# suliss-sensor-board.net
KiCad netlist of a schematic drawn in EAGLE
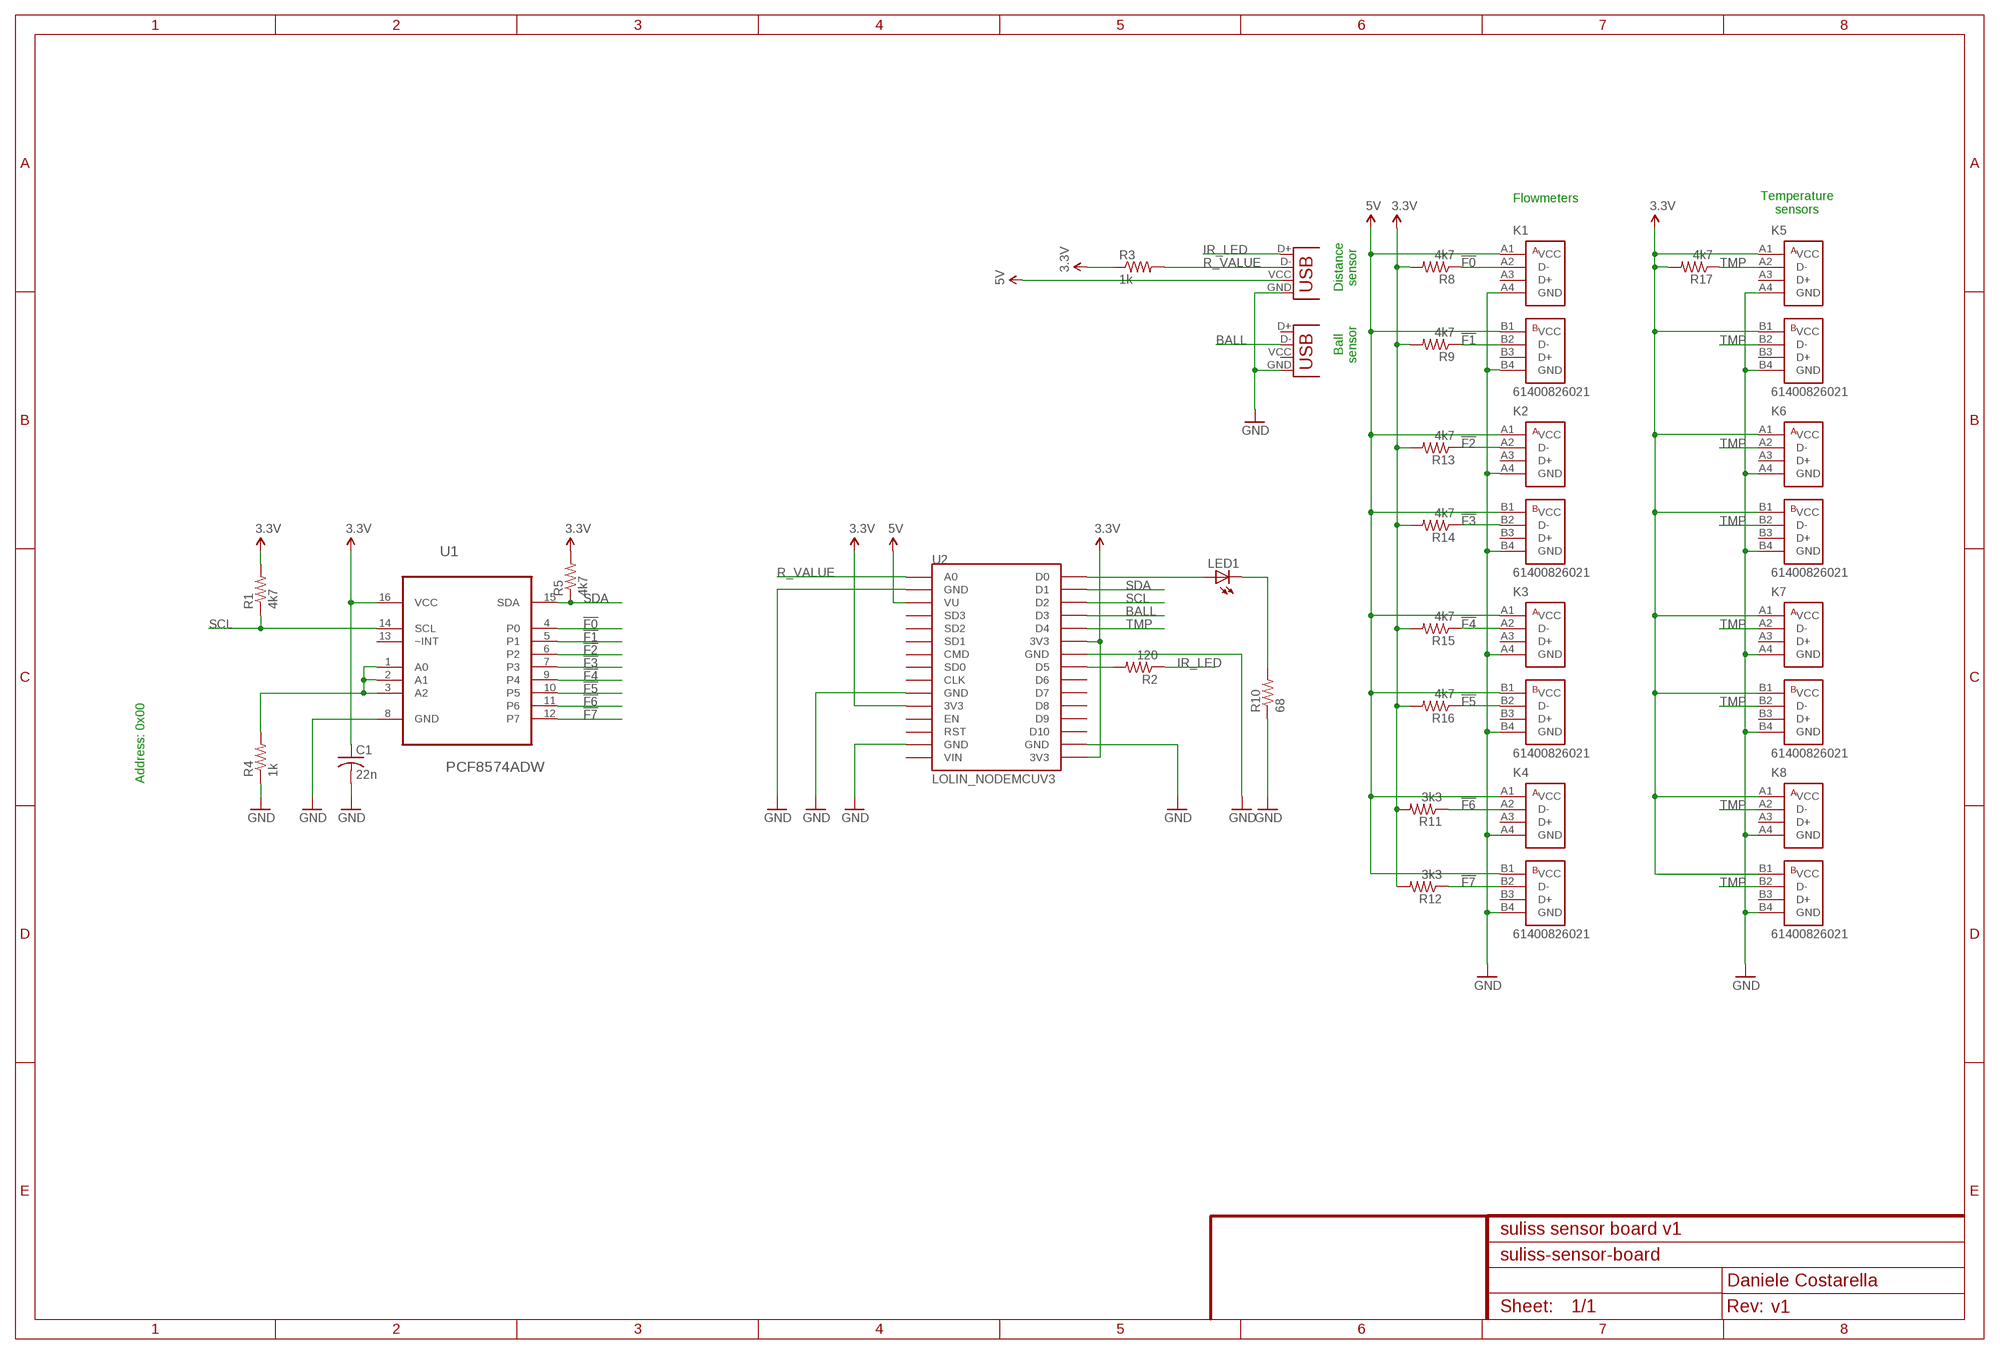
[diagram p0: schematic, sheet 1]

(export (version "E")
  (design (tool "Eeschema 10.0.6"))
  (components
    (comp (ref "C1")
      (value "22n")
      (footprint "eagle-import:C1206")
      (libsource (lib "eagle-import") (part "C-USC1206"))
    )
    (comp (ref "JP1")
      (value "USB-A-H")
      (footprint "eagle-import:USB-A-VERT")
      (libsource (lib "eagle-import") (part "USB-A-H"))
    )
    (comp (ref "JP2")
      (value "USB-A-H")
      (footprint "eagle-import:USB-A-VERT")
      (libsource (lib "eagle-import") (part "USB-A-H"))
    )
    (comp (ref "K1")
      (value "61400826021")
      (footprint "eagle-import:61400826021")
      (libsource (lib "eagle-import") (part "61400826021"))
    )
    (comp (ref "K2")
      (value "61400826021")
      (footprint "eagle-import:61400826021")
      (libsource (lib "eagle-import") (part "61400826021"))
    )
    (comp (ref "K3")
      (value "61400826021")
      (footprint "eagle-import:61400826021")
      (libsource (lib "eagle-import") (part "61400826021"))
    )
    (comp (ref "K4")
      (value "61400826021")
      (footprint "eagle-import:61400826021")
      (libsource (lib "eagle-import") (part "61400826021"))
    )
    (comp (ref "K5")
      (value "61400826021")
      (footprint "eagle-import:61400826021")
      (libsource (lib "eagle-import") (part "61400826021"))
    )
    (comp (ref "K6")
      (value "61400826021")
      (footprint "eagle-import:61400826021")
      (libsource (lib "eagle-import") (part "61400826021"))
    )
    (comp (ref "K7")
      (value "61400826021")
      (footprint "eagle-import:61400826021")
      (libsource (lib "eagle-import") (part "61400826021"))
    )
    (comp (ref "K8")
      (value "61400826021")
      (footprint "eagle-import:61400826021")
      (libsource (lib "eagle-import") (part "61400826021"))
    )
    (comp (ref "LED1")
      (value "LEDCHIP-LED0603")
      (footprint "eagle-import:CHIP-LED0603")
      (libsource (lib "eagle-import") (part "LEDCHIP-LED0603"))
    )
    (comp (ref "R1")
      (value "4k7")
      (footprint "eagle-import:R0603")
      (libsource (lib "eagle-import") (part "R-US_R0603"))
    )
    (comp (ref "R2")
      (value "120")
      (footprint "eagle-import:R0603")
      (libsource (lib "eagle-import") (part "R-US_R0603"))
    )
    (comp (ref "R3")
      (value "1k")
      (footprint "eagle-import:R0603")
      (libsource (lib "eagle-import") (part "R-US_R0603"))
    )
    (comp (ref "R4")
      (value "1k")
      (footprint "eagle-import:R0603")
      (libsource (lib "eagle-import") (part "R-US_R0603"))
    )
    (comp (ref "R5")
      (value "4k7")
      (footprint "eagle-import:R0603")
      (libsource (lib "eagle-import") (part "R-US_R0603"))
    )
    (comp (ref "R8")
      (value "4k7")
      (footprint "eagle-import:R0603")
      (libsource (lib "eagle-import") (part "R-US_R0603"))
    )
    (comp (ref "R9")
      (value "4k7")
      (footprint "eagle-import:R0603")
      (libsource (lib "eagle-import") (part "R-US_R0603"))
    )
    (comp (ref "R10")
      (value "68")
      (footprint "eagle-import:R0603")
      (libsource (lib "eagle-import") (part "R-US_R0603"))
    )
    (comp (ref "R11")
      (value "3k3")
      (footprint "eagle-import:R0603")
      (libsource (lib "eagle-import") (part "R-US_R0603"))
    )
    (comp (ref "R12")
      (value "3k3")
      (footprint "eagle-import:R0603")
      (libsource (lib "eagle-import") (part "R-US_R0603"))
    )
    (comp (ref "R13")
      (value "4k7")
      (footprint "eagle-import:R0603")
      (libsource (lib "eagle-import") (part "R-US_R0603"))
    )
    (comp (ref "R14")
      (value "4k7")
      (footprint "eagle-import:R0603")
      (libsource (lib "eagle-import") (part "R-US_R0603"))
    )
    (comp (ref "R15")
      (value "4k7")
      (footprint "eagle-import:R0603")
      (libsource (lib "eagle-import") (part "R-US_R0603"))
    )
    (comp (ref "R16")
      (value "4k7")
      (footprint "eagle-import:R0603")
      (libsource (lib "eagle-import") (part "R-US_R0603"))
    )
    (comp (ref "R17")
      (value "4k7")
      (footprint "eagle-import:R0603")
      (libsource (lib "eagle-import") (part "R-US_R0603"))
    )
    (comp (ref "U1")
      (value "PCF8574ADW")
      (footprint "eagle-import:SOIC127P1030X265-16N")
      (libsource (lib "eagle-import") (part "PCF8574ADW"))
    )
    (comp (ref "U2")
      (value "LOLIN_NODEMCUV3")
      (footprint "eagle-import:ESP12E_DEVKIT_CHINA")
      (libsource (lib "eagle-import") (part "LOLIN_NODEMCUV3"))
    )
  )
  (nets
    (net (code "1") (name "/BALL") (class "Default")
      (node (ref "JP2") (pin "D-") (pinfunction "D-_D-") (pintype "bidirectional"))
      (node (ref "U2") (pin "D3") (pinfunction "D3_D3") (pintype "bidirectional"))
    )
    (net (code "2") (name "/IR_LED") (class "Default")
      (node (ref "JP1") (pin "D+") (pinfunction "D+_D+") (pintype "bidirectional"))
      (node (ref "R2") (pin "1") (pinfunction "1_1") (pintype "passive"))
    )
    (net (code "3") (name "/R_VALUE") (class "Default")
      (node (ref "JP1") (pin "D-") (pinfunction "D-_D-") (pintype "bidirectional"))
      (node (ref "R3") (pin "2") (pinfunction "2_2") (pintype "passive"))
      (node (ref "U2") (pin "A0") (pinfunction "A0_A0") (pintype "bidirectional"))
    )
    (net (code "4") (name "/SCL") (class "Default")
      (node (ref "R1") (pin "1") (pinfunction "1_1") (pintype "passive"))
      (node (ref "U1") (pin "14") (pinfunction "SCL_14") (pintype "input"))
      (node (ref "U2") (pin "D2") (pinfunction "D2_D2") (pintype "bidirectional"))
    )
    (net (code "5") (name "/SDA") (class "Default")
      (node (ref "R5") (pin "1") (pinfunction "1_1") (pintype "passive"))
      (node (ref "U1") (pin "15") (pinfunction "SDA_15") (pintype "bidirectional"))
      (node (ref "U2") (pin "D1") (pinfunction "D1_D1") (pintype "bidirectional"))
    )
    (net (code "6") (name "/TMP") (class "Default")
      (node (ref "K5") (pin "A2") (pinfunction "D-_A2") (pintype "bidirectional"))
      (node (ref "K5") (pin "B2") (pinfunction "D-_B2") (pintype "bidirectional"))
      (node (ref "K6") (pin "A2") (pinfunction "D-_A2") (pintype "bidirectional"))
      (node (ref "K6") (pin "B2") (pinfunction "D-_B2") (pintype "bidirectional"))
      (node (ref "K7") (pin "A2") (pinfunction "D-_A2") (pintype "bidirectional"))
      (node (ref "K7") (pin "B2") (pinfunction "D-_B2") (pintype "bidirectional"))
      (node (ref "K8") (pin "A2") (pinfunction "D-_A2") (pintype "bidirectional"))
      (node (ref "K8") (pin "B2") (pinfunction "D-_B2") (pintype "bidirectional"))
      (node (ref "R17") (pin "1") (pinfunction "1_1") (pintype "passive"))
      (node (ref "U2") (pin "D4") (pinfunction "D4_D4") (pintype "bidirectional"))
    )
    (net (code "7") (name "/~{F0}") (class "Default")
      (node (ref "K1") (pin "A2") (pinfunction "D-_A2") (pintype "bidirectional"))
      (node (ref "R8") (pin "1") (pinfunction "1_1") (pintype "passive"))
      (node (ref "U1") (pin "4") (pinfunction "P0_4") (pintype "bidirectional"))
    )
    (net (code "8") (name "/~{F1}") (class "Default")
      (node (ref "K1") (pin "B2") (pinfunction "D-_B2") (pintype "bidirectional"))
      (node (ref "R9") (pin "1") (pinfunction "1_1") (pintype "passive"))
      (node (ref "U1") (pin "5") (pinfunction "P1_5") (pintype "bidirectional"))
    )
    (net (code "9") (name "/~{F2}") (class "Default")
      (node (ref "K2") (pin "A2") (pinfunction "D-_A2") (pintype "bidirectional"))
      (node (ref "R13") (pin "1") (pinfunction "1_1") (pintype "passive"))
      (node (ref "U1") (pin "6") (pinfunction "P2_6") (pintype "bidirectional"))
    )
    (net (code "10") (name "/~{F3}") (class "Default")
      (node (ref "K2") (pin "B2") (pinfunction "D-_B2") (pintype "bidirectional"))
      (node (ref "R14") (pin "1") (pinfunction "1_1") (pintype "passive"))
      (node (ref "U1") (pin "7") (pinfunction "P3_7") (pintype "bidirectional"))
    )
    (net (code "11") (name "/~{F4}") (class "Default")
      (node (ref "K3") (pin "A2") (pinfunction "D-_A2") (pintype "bidirectional"))
      (node (ref "R15") (pin "1") (pinfunction "1_1") (pintype "passive"))
      (node (ref "U1") (pin "9") (pinfunction "P4_9") (pintype "bidirectional"))
    )
    (net (code "12") (name "/~{F5}") (class "Default")
      (node (ref "K3") (pin "B2") (pinfunction "D-_B2") (pintype "bidirectional"))
      (node (ref "R16") (pin "1") (pinfunction "1_1") (pintype "passive"))
      (node (ref "U1") (pin "10") (pinfunction "P5_10") (pintype "bidirectional"))
    )
    (net (code "13") (name "/~{F6}") (class "Default")
      (node (ref "K4") (pin "A2") (pinfunction "D-_A2") (pintype "bidirectional"))
      (node (ref "R11") (pin "1") (pinfunction "1_1") (pintype "passive"))
      (node (ref "U1") (pin "11") (pinfunction "P6_11") (pintype "bidirectional"))
    )
    (net (code "14") (name "/~{F7}") (class "Default")
      (node (ref "K4") (pin "B2") (pinfunction "D-_B2") (pintype "bidirectional"))
      (node (ref "R12") (pin "1") (pinfunction "1_1") (pintype "passive"))
      (node (ref "U1") (pin "12") (pinfunction "P7_12") (pintype "bidirectional"))
    )
    (net (code "15") (name "3.3V") (class "Default")
      (node (ref "C1") (pin "1") (pinfunction "1_1") (pintype "passive"))
      (node (ref "K5") (pin "A1") (pinfunction "VCC_A1") (pintype "bidirectional"))
      (node (ref "K5") (pin "B1") (pinfunction "VCC_B1") (pintype "bidirectional"))
      (node (ref "K6") (pin "A1") (pinfunction "VCC_A1") (pintype "bidirectional"))
      (node (ref "K6") (pin "B1") (pinfunction "VCC_B1") (pintype "bidirectional"))
      (node (ref "K7") (pin "A1") (pinfunction "VCC_A1") (pintype "bidirectional"))
      (node (ref "K7") (pin "B1") (pinfunction "VCC_B1") (pintype "bidirectional"))
      (node (ref "K8") (pin "A1") (pinfunction "VCC_A1") (pintype "bidirectional"))
      (node (ref "K8") (pin "B1") (pinfunction "VCC_B1") (pintype "bidirectional"))
      (node (ref "R1") (pin "2") (pinfunction "2_2") (pintype "passive"))
      (node (ref "R11") (pin "2") (pinfunction "2_2") (pintype "passive"))
      (node (ref "R12") (pin "2") (pinfunction "2_2") (pintype "passive"))
      (node (ref "R13") (pin "2") (pinfunction "2_2") (pintype "passive"))
      (node (ref "R14") (pin "2") (pinfunction "2_2") (pintype "passive"))
      (node (ref "R15") (pin "2") (pinfunction "2_2") (pintype "passive"))
      (node (ref "R16") (pin "2") (pinfunction "2_2") (pintype "passive"))
      (node (ref "R17") (pin "2") (pinfunction "2_2") (pintype "passive"))
      (node (ref "R3") (pin "1") (pinfunction "1_1") (pintype "passive"))
      (node (ref "R5") (pin "2") (pinfunction "2_2") (pintype "passive"))
      (node (ref "R8") (pin "2") (pinfunction "2_2") (pintype "passive"))
      (node (ref "R9") (pin "2") (pinfunction "2_2") (pintype "passive"))
      (node (ref "U1") (pin "16") (pinfunction "VCC_16") (pintype "power_in"))
      (node (ref "U2") (pin "3V3@0") (pinfunction "3V3_3V3@0") (pintype "bidirectional"))
      (node (ref "U2") (pin "3V3@1") (pinfunction "3V3_3V3@1") (pintype "bidirectional"))
      (node (ref "U2") (pin "3V3@2") (pinfunction "3V3_3V3@2") (pintype "bidirectional"))
    )
    (net (code "16") (name "5V") (class "Default")
      (node (ref "JP1") (pin "VCC") (pinfunction "VBUS_VCC") (pintype "bidirectional"))
      (node (ref "K1") (pin "A1") (pinfunction "VCC_A1") (pintype "bidirectional"))
      (node (ref "K1") (pin "B1") (pinfunction "VCC_B1") (pintype "bidirectional"))
      (node (ref "K2") (pin "A1") (pinfunction "VCC_A1") (pintype "bidirectional"))
      (node (ref "K2") (pin "B1") (pinfunction "VCC_B1") (pintype "bidirectional"))
      (node (ref "K3") (pin "A1") (pinfunction "VCC_A1") (pintype "bidirectional"))
      (node (ref "K3") (pin "B1") (pinfunction "VCC_B1") (pintype "bidirectional"))
      (node (ref "K4") (pin "A1") (pinfunction "VCC_A1") (pintype "bidirectional"))
      (node (ref "K4") (pin "B1") (pinfunction "VCC_B1") (pintype "bidirectional"))
      (node (ref "U2") (pin "VU") (pinfunction "VU_VU") (pintype "bidirectional"))
    )
    (net (code "17") (name "GND") (class "Default")
      (node (ref "C1") (pin "2") (pinfunction "2_2") (pintype "passive"))
      (node (ref "JP1") (pin "GND") (pinfunction "GND_GND") (pintype "bidirectional"))
      (node (ref "JP2") (pin "GND") (pinfunction "GND_GND") (pintype "bidirectional"))
      (node (ref "K1") (pin "A4") (pinfunction "GND_A4") (pintype "bidirectional"))
      (node (ref "K1") (pin "B4") (pinfunction "GND_B4") (pintype "bidirectional"))
      (node (ref "K2") (pin "A4") (pinfunction "GND_A4") (pintype "bidirectional"))
      (node (ref "K2") (pin "B4") (pinfunction "GND_B4") (pintype "bidirectional"))
      (node (ref "K3") (pin "A4") (pinfunction "GND_A4") (pintype "bidirectional"))
      (node (ref "K3") (pin "B4") (pinfunction "GND_B4") (pintype "bidirectional"))
      (node (ref "K4") (pin "A4") (pinfunction "GND_A4") (pintype "bidirectional"))
      (node (ref "K4") (pin "B4") (pinfunction "GND_B4") (pintype "bidirectional"))
      (node (ref "K5") (pin "A4") (pinfunction "GND_A4") (pintype "bidirectional"))
      (node (ref "K5") (pin "B4") (pinfunction "GND_B4") (pintype "bidirectional"))
      (node (ref "K6") (pin "A4") (pinfunction "GND_A4") (pintype "bidirectional"))
      (node (ref "K6") (pin "B4") (pinfunction "GND_B4") (pintype "bidirectional"))
      (node (ref "K7") (pin "A4") (pinfunction "GND_A4") (pintype "bidirectional"))
      (node (ref "K7") (pin "B4") (pinfunction "GND_B4") (pintype "bidirectional"))
      (node (ref "K8") (pin "A4") (pinfunction "GND_A4") (pintype "bidirectional"))
      (node (ref "K8") (pin "B4") (pinfunction "GND_B4") (pintype "bidirectional"))
      (node (ref "R10") (pin "1") (pinfunction "1_1") (pintype "passive"))
      (node (ref "R4") (pin "1") (pinfunction "1_1") (pintype "passive"))
      (node (ref "U1") (pin "8") (pinfunction "GND_8") (pintype "passive"))
      (node (ref "U2") (pin "GND@0") (pinfunction "GND_GND@0") (pintype "bidirectional"))
      (node (ref "U2") (pin "GND@1") (pinfunction "GND_GND@1") (pintype "bidirectional"))
      (node (ref "U2") (pin "GND@2") (pinfunction "GND_GND@2") (pintype "bidirectional"))
      (node (ref "U2") (pin "GND@3") (pinfunction "GND_GND@3") (pintype "bidirectional"))
      (node (ref "U2") (pin "GND@4") (pinfunction "GND_GND@4") (pintype "bidirectional"))
    )
    (net (code "18") (name "Net-(LED1-PadA)") (class "Default")
      (node (ref "LED1") (pin "A") (pinfunction "A_A") (pintype "passive"))
      (node (ref "U2") (pin "D0") (pinfunction "D0_D0") (pintype "bidirectional"))
    )
    (net (code "19") (name "Net-(LED1-PadC)") (class "Default")
      (node (ref "LED1") (pin "C") (pinfunction "C_C") (pintype "passive"))
      (node (ref "R10") (pin "2") (pinfunction "2_2") (pintype "passive"))
    )
    (net (code "20") (name "Net-(R2-Pad2)") (class "Default")
      (node (ref "R2") (pin "2") (pinfunction "2_2") (pintype "passive"))
      (node (ref "U2") (pin "D5") (pinfunction "D5_D5") (pintype "bidirectional"))
    )
    (net (code "21") (name "Net-(U1-A0)") (class "Default")
      (node (ref "R4") (pin "2") (pinfunction "2_2") (pintype "passive"))
      (node (ref "U1") (pin "1") (pinfunction "A0_1") (pintype "input"))
      (node (ref "U1") (pin "2") (pinfunction "A1_2") (pintype "input"))
      (node (ref "U1") (pin "3") (pinfunction "A2_3") (pintype "input"))
    )
    (net (code "22") (name "unconnected-(JP2-PadD+)") (class "Default")
      (node (ref "JP2") (pin "D+") (pinfunction "D+_D+") (pintype "bidirectional"))
    )
    (net (code "23") (name "unconnected-(JP2-VBUS-PadVCC)") (class "Default")
      (node (ref "JP2") (pin "VCC") (pinfunction "VBUS_VCC") (pintype "bidirectional"))
    )
    (net (code "24") (name "unconnected-(K1-D+-PadA3)") (class "Default")
      (node (ref "K1") (pin "A3") (pinfunction "D+_A3") (pintype "bidirectional"))
    )
    (net (code "25") (name "unconnected-(K1-D+-PadB3)") (class "Default")
      (node (ref "K1") (pin "B3") (pinfunction "D+_B3") (pintype "bidirectional"))
    )
    (net (code "26") (name "unconnected-(K2-D+-PadA3)") (class "Default")
      (node (ref "K2") (pin "A3") (pinfunction "D+_A3") (pintype "bidirectional"))
    )
    (net (code "27") (name "unconnected-(K2-D+-PadB3)") (class "Default")
      (node (ref "K2") (pin "B3") (pinfunction "D+_B3") (pintype "bidirectional"))
    )
    (net (code "28") (name "unconnected-(K3-D+-PadA3)") (class "Default")
      (node (ref "K3") (pin "A3") (pinfunction "D+_A3") (pintype "bidirectional"))
    )
    (net (code "29") (name "unconnected-(K3-D+-PadB3)") (class "Default")
      (node (ref "K3") (pin "B3") (pinfunction "D+_B3") (pintype "bidirectional"))
    )
    (net (code "30") (name "unconnected-(K4-D+-PadA3)") (class "Default")
      (node (ref "K4") (pin "A3") (pinfunction "D+_A3") (pintype "bidirectional"))
    )
    (net (code "31") (name "unconnected-(K4-D+-PadB3)") (class "Default")
      (node (ref "K4") (pin "B3") (pinfunction "D+_B3") (pintype "bidirectional"))
    )
    (net (code "32") (name "unconnected-(K5-D+-PadA3)") (class "Default")
      (node (ref "K5") (pin "A3") (pinfunction "D+_A3") (pintype "bidirectional"))
    )
    (net (code "33") (name "unconnected-(K5-D+-PadB3)") (class "Default")
      (node (ref "K5") (pin "B3") (pinfunction "D+_B3") (pintype "bidirectional"))
    )
    (net (code "34") (name "unconnected-(K6-D+-PadA3)") (class "Default")
      (node (ref "K6") (pin "A3") (pinfunction "D+_A3") (pintype "bidirectional"))
    )
    (net (code "35") (name "unconnected-(K6-D+-PadB3)") (class "Default")
      (node (ref "K6") (pin "B3") (pinfunction "D+_B3") (pintype "bidirectional"))
    )
    (net (code "36") (name "unconnected-(K7-D+-PadA3)") (class "Default")
      (node (ref "K7") (pin "A3") (pinfunction "D+_A3") (pintype "bidirectional"))
    )
    (net (code "37") (name "unconnected-(K7-D+-PadB3)") (class "Default")
      (node (ref "K7") (pin "B3") (pinfunction "D+_B3") (pintype "bidirectional"))
    )
    (net (code "38") (name "unconnected-(K8-D+-PadA3)") (class "Default")
      (node (ref "K8") (pin "A3") (pinfunction "D+_A3") (pintype "bidirectional"))
    )
    (net (code "39") (name "unconnected-(K8-D+-PadB3)") (class "Default")
      (node (ref "K8") (pin "B3") (pinfunction "D+_B3") (pintype "bidirectional"))
    )
    (net (code "40") (name "unconnected-(U1-~{INT}-Pad13)") (class "Default")
      (node (ref "U1") (pin "13") (pinfunction "~{INT}_13") (pintype "input"))
    )
    (net (code "41") (name "unconnected-(U2-D9-PadRX)") (class "Default")
      (node (ref "U2") (pin "RX") (pinfunction "D9_RX") (pintype "bidirectional"))
    )
    (net (code "42") (name "unconnected-(U2-D10-PadTX)") (class "Default")
      (node (ref "U2") (pin "TX") (pinfunction "D10_TX") (pintype "bidirectional"))
    )
    (net (code "43") (name "unconnected-(U2-PadCLK)") (class "Default")
      (node (ref "U2") (pin "CLK") (pinfunction "CLK_CLK") (pintype "bidirectional"))
    )
    (net (code "44") (name "unconnected-(U2-PadCMD)") (class "Default")
      (node (ref "U2") (pin "CMD") (pinfunction "CMD_CMD") (pintype "bidirectional"))
    )
    (net (code "45") (name "unconnected-(U2-PadD6)") (class "Default")
      (node (ref "U2") (pin "D6") (pinfunction "D6_D6") (pintype "bidirectional"))
    )
    (net (code "46") (name "unconnected-(U2-PadD7)") (class "Default")
      (node (ref "U2") (pin "D7") (pinfunction "D7_D7") (pintype "bidirectional"))
    )
    (net (code "47") (name "unconnected-(U2-PadD8)") (class "Default")
      (node (ref "U2") (pin "D8") (pinfunction "D8_D8") (pintype "bidirectional"))
    )
    (net (code "48") (name "unconnected-(U2-PadEN)") (class "Default")
      (node (ref "U2") (pin "EN") (pinfunction "EN_EN") (pintype "bidirectional"))
    )
    (net (code "49") (name "unconnected-(U2-PadRST)") (class "Default")
      (node (ref "U2") (pin "RST") (pinfunction "RST_RST") (pintype "bidirectional"))
    )
    (net (code "50") (name "unconnected-(U2-PadSD0)") (class "Default")
      (node (ref "U2") (pin "SD0") (pinfunction "SD0_SD0") (pintype "bidirectional"))
    )
    (net (code "51") (name "unconnected-(U2-PadSD1)") (class "Default")
      (node (ref "U2") (pin "SD1") (pinfunction "SD1_SD1") (pintype "bidirectional"))
    )
    (net (code "52") (name "unconnected-(U2-PadSD2)") (class "Default")
      (node (ref "U2") (pin "SD2") (pinfunction "SD2_SD2") (pintype "bidirectional"))
    )
    (net (code "53") (name "unconnected-(U2-PadSD3)") (class "Default")
      (node (ref "U2") (pin "SD3") (pinfunction "SD3_SD3") (pintype "bidirectional"))
    )
    (net (code "54") (name "unconnected-(U2-PadVIN)") (class "Default")
      (node (ref "U2") (pin "VIN") (pinfunction "VIN_VIN") (pintype "bidirectional"))
    )
  )
)
